# WaterFlowSensor-RJ11-Adaptor-V1_0.net
KiCad netlist of a schematic drawn in EAGLE
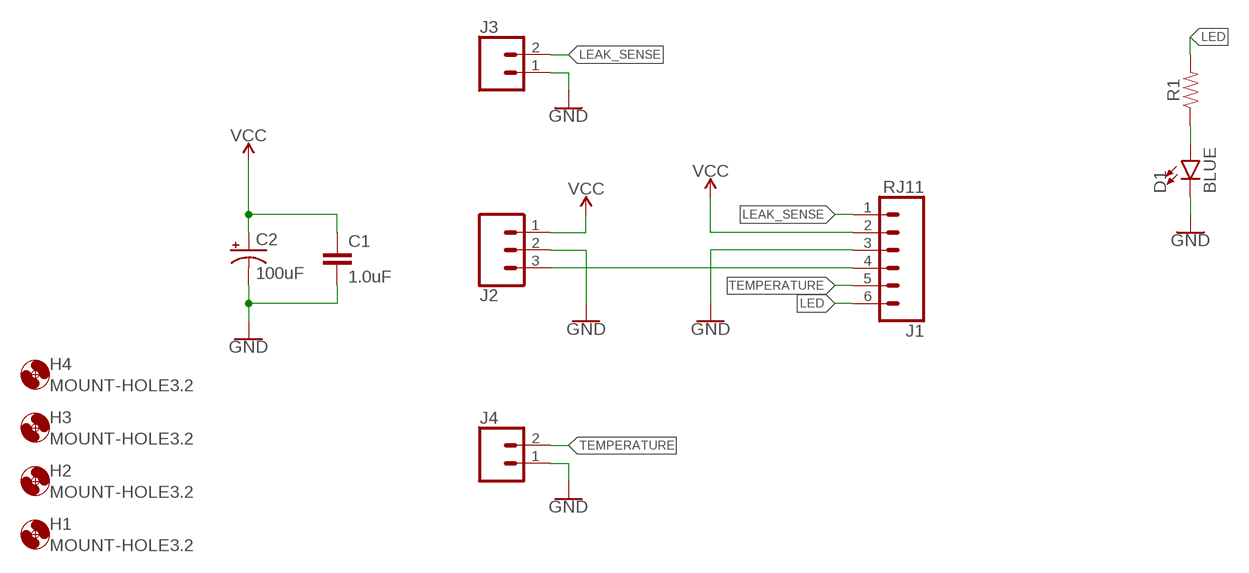
[diagram p0: schematic, sheet 1]

(export (version "E")
  (design (tool "Eeschema 10.0.6"))
  (components
    (comp (ref "C1")
      (value "1.0uF")
      (footprint "eagle-import:0805")
      (libsource (lib "eagle-import") (part "1.0UF-0805-25V-(+80/-20%)"))
    )
    (comp (ref "C2")
      (value "100uF")
      (footprint "eagle-import:CPOL-RADIAL-2.5MM-6.5MM")
      (libsource (lib "eagle-import") (part "100UF-POLAR-RADIAL-2.5MM-25V-20%"))
    )
    (comp (ref "D1")
      (value "BLUE")
      (footprint "eagle-import:LED-1206")
      (libsource (lib "eagle-import") (part "LED-BLUE1206"))
    )
    (comp (ref "H1")
      (value "MOUNT-HOLE3.2")
      (footprint "eagle-import:3,2")
      (libsource (lib "eagle-import") (part "MOUNT-HOLE3.2"))
    )
    (comp (ref "H2")
      (value "MOUNT-HOLE3.2")
      (footprint "eagle-import:3,2")
      (libsource (lib "eagle-import") (part "MOUNT-HOLE3.2"))
    )
    (comp (ref "H3")
      (value "MOUNT-HOLE3.2")
      (footprint "eagle-import:3,2")
      (libsource (lib "eagle-import") (part "MOUNT-HOLE3.2"))
    )
    (comp (ref "H4")
      (value "MOUNT-HOLE3.2")
      (footprint "eagle-import:3,2")
      (libsource (lib "eagle-import") (part "MOUNT-HOLE3.2"))
    )
    (comp (ref "J1")
      (value "RJ11")
      (footprint "eagle-import:RJ11-6")
      (libsource (lib "eagle-import") (part "RJ11-6"))
    )
    (comp (ref "J2")
      (value "CONN_03JST-HX-PTH-VERT")
      (footprint "eagle-import:JST-HX-3-PTH-VERT")
      (libsource (lib "eagle-import") (part "CONN_03JST-HX-PTH-VERT"))
    )
    (comp (ref "J3")
      (value "CONN_02")
      (footprint "eagle-import:1X02")
      (libsource (lib "eagle-import") (part "CONN_02"))
    )
    (comp (ref "J4")
      (value "CONN_02POLAR")
      (footprint "eagle-import:MOLEX-1X2")
      (libsource (lib "eagle-import") (part "CONN_02POLAR"))
    )
    (comp (ref "R1")
      (value "RESISTOR0805")
      (footprint "eagle-import:0805")
      (libsource (lib "eagle-import") (part "RESISTOR0805"))
    )
  )
  (nets
    (net (code "1") (name "GND") (class "Default")
      (node (ref "C1") (pin "2") (pinfunction "2_2") (pintype "passive"))
      (node (ref "C2") (pin "2") (pinfunction "-_2") (pintype "passive"))
      (node (ref "D1") (pin "C") (pinfunction "C_C") (pintype "passive"))
      (node (ref "J1") (pin "3") (pinfunction "3_3") (pintype "passive"))
      (node (ref "J2") (pin "2") (pinfunction "2_2") (pintype "passive"))
      (node (ref "J3") (pin "1") (pinfunction "1_1") (pintype "passive"))
      (node (ref "J4") (pin "1") (pinfunction "1_1") (pintype "passive"))
    )
    (net (code "2") (name "LEAK_SENSE") (class "Default")
      (node (ref "J1") (pin "1") (pinfunction "1_1") (pintype "passive"))
      (node (ref "J3") (pin "2") (pinfunction "2_2") (pintype "passive"))
    )
    (net (code "3") (name "LED") (class "Default")
      (node (ref "J1") (pin "6") (pinfunction "6_6") (pintype "passive"))
      (node (ref "R1") (pin "2") (pinfunction "2_2") (pintype "passive"))
    )
    (net (code "4") (name "Net-(D1-PadA)") (class "Default")
      (node (ref "D1") (pin "A") (pinfunction "A_A") (pintype "passive"))
      (node (ref "R1") (pin "1") (pinfunction "1_1") (pintype "passive"))
    )
    (net (code "5") (name "Net-(J1-Pad4)") (class "Default")
      (node (ref "J1") (pin "4") (pinfunction "4_4") (pintype "passive"))
      (node (ref "J2") (pin "3") (pinfunction "3_3") (pintype "passive"))
    )
    (net (code "6") (name "TEMPERATURE") (class "Default")
      (node (ref "J1") (pin "5") (pinfunction "5_5") (pintype "passive"))
      (node (ref "J4") (pin "2") (pinfunction "2_2") (pintype "passive"))
    )
    (net (code "7") (name "VCC") (class "Default")
      (node (ref "C1") (pin "1") (pinfunction "1_1") (pintype "passive"))
      (node (ref "C2") (pin "1") (pinfunction "+_1") (pintype "passive"))
      (node (ref "J1") (pin "2") (pinfunction "2_2") (pintype "passive"))
      (node (ref "J2") (pin "1") (pinfunction "1_1") (pintype "passive"))
    )
  )
)
